# MYC_Klimasensor.net
KiCad netlist of a schematic drawn in EAGLE
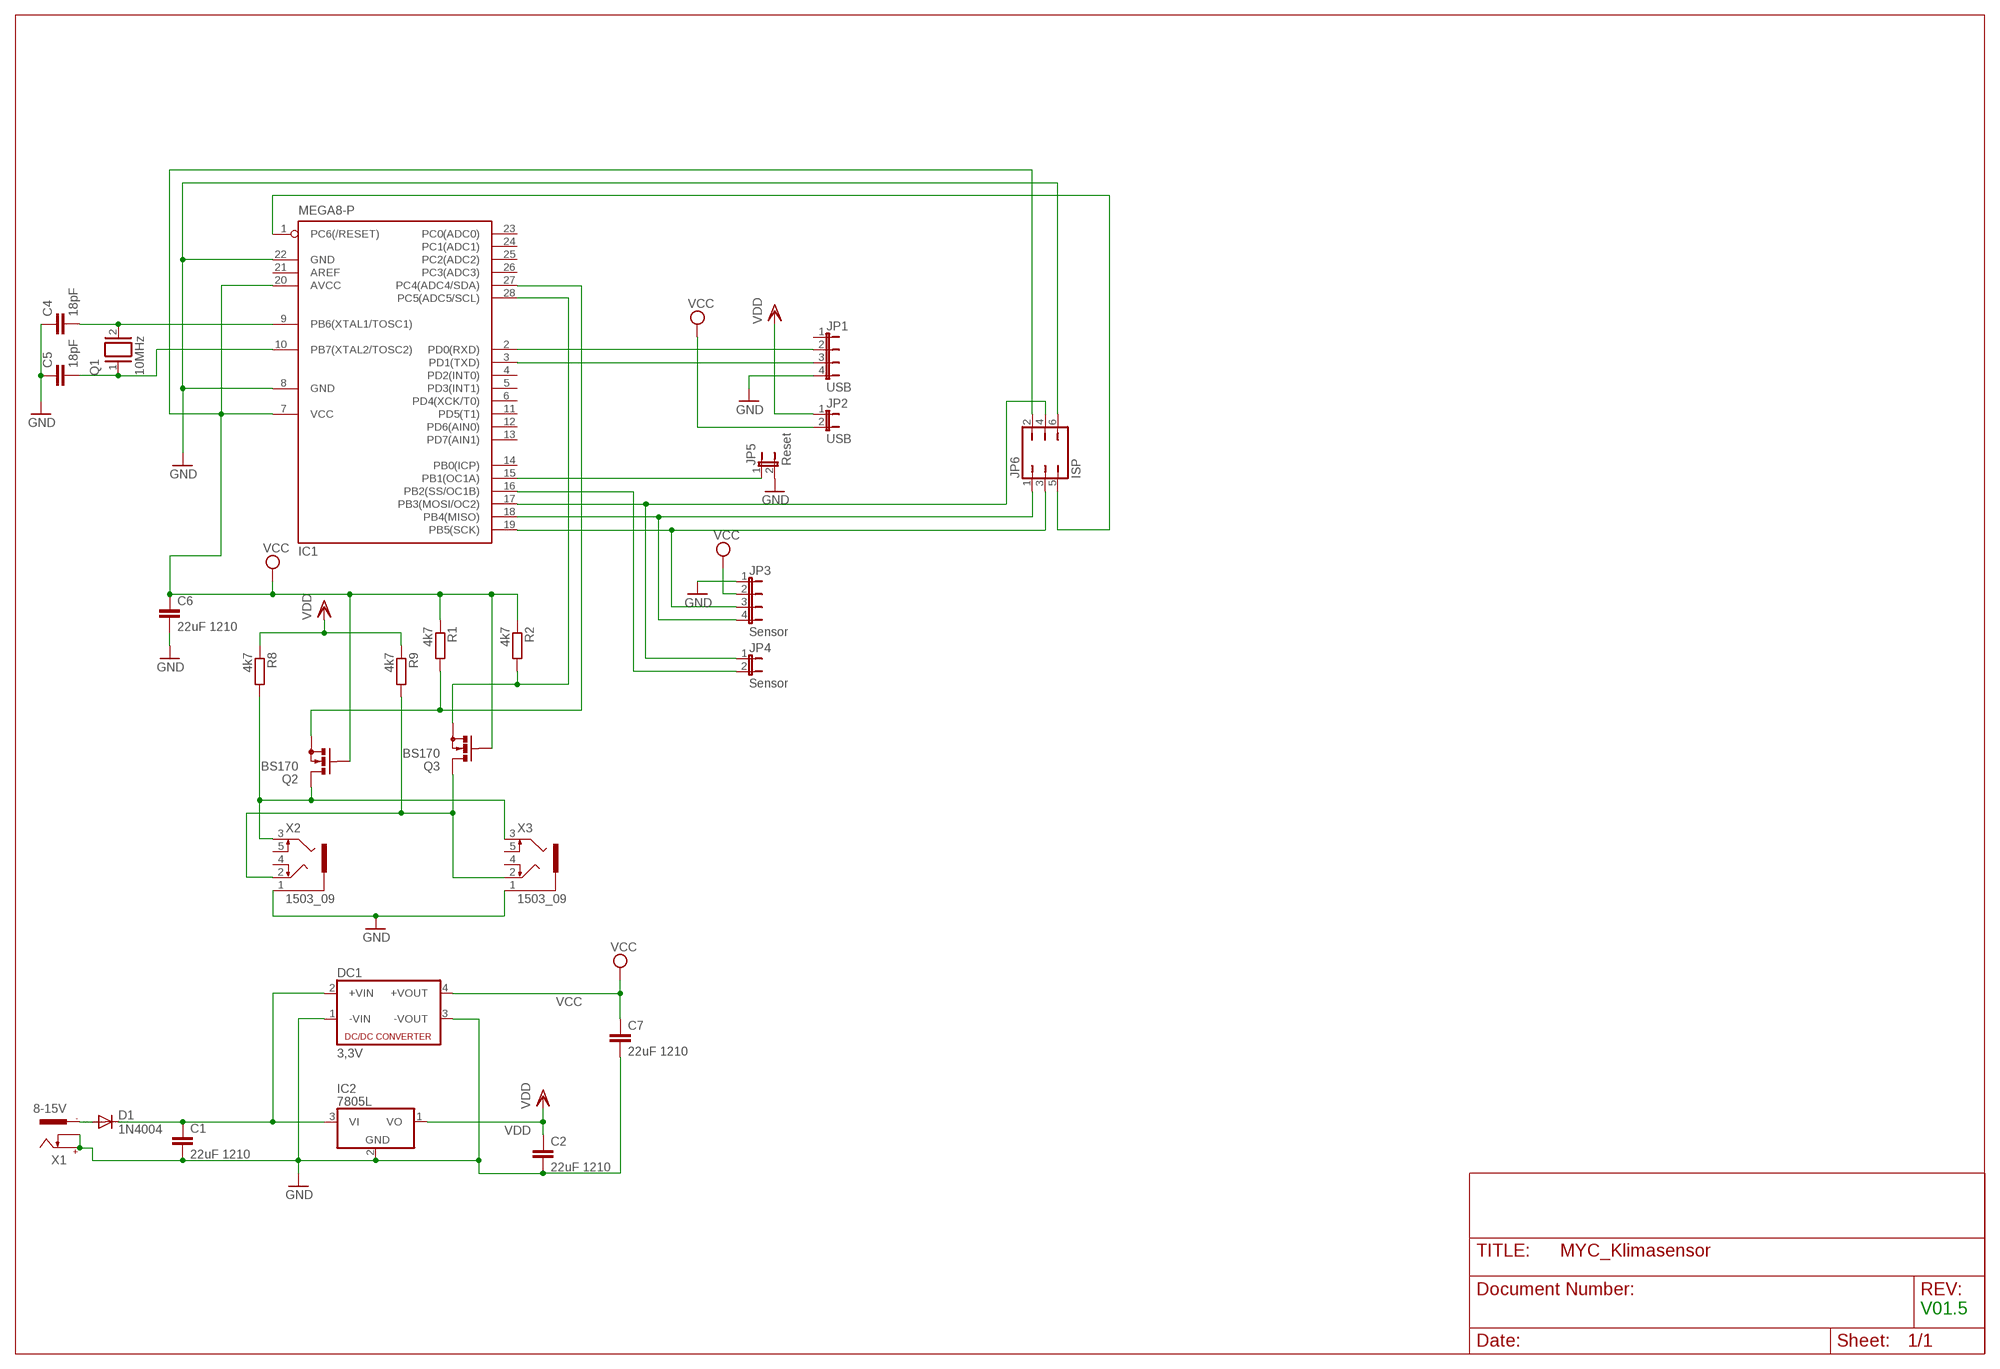
[diagram p0: schematic, sheet 1]

(export (version "E")
  (design (tool "Eeschema 10.0.6"))
  (components
    (comp (ref "C1")
      (value "22uF 1210")
      (footprint "eagle-import:C1206")
      (libsource (lib "eagle-import") (part "C-EUC1206"))
    )
    (comp (ref "C2")
      (value "22uF 1210")
      (footprint "eagle-import:C1206")
      (libsource (lib "eagle-import") (part "C-EUC1206"))
    )
    (comp (ref "C4")
      (value "18pF")
      (footprint "eagle-import:C025-025X050")
      (libsource (lib "eagle-import") (part "resistor_C-EU025-025X050"))
    )
    (comp (ref "C5")
      (value "18pF")
      (footprint "eagle-import:C025-025X050")
      (libsource (lib "eagle-import") (part "resistor_C-EU025-025X050"))
    )
    (comp (ref "C6")
      (value "22uF 1210")
      (footprint "eagle-import:C1206")
      (libsource (lib "eagle-import") (part "C-EUC1206"))
    )
    (comp (ref "C7")
      (value "22uF 1210")
      (footprint "eagle-import:C1206")
      (libsource (lib "eagle-import") (part "C-EUC1206"))
    )
    (comp (ref "D1")
      (value "1N4004")
      (footprint "eagle-import:DO41-10")
      (libsource (lib "eagle-import") (part "1N4004"))
    )
    (comp (ref "DC1")
      (value "3,3V")
      (footprint "eagle-import:NME")
      (fields (field (name "MF") "C & D TECHNOLOGIES, INC") (field (name "MPN") "NME1205D"))
      (libsource (lib "eagle-import") (part "NME"))
    )
    (comp (ref "IC1")
      (value "MEGA8-P")
      (footprint "eagle-import:DIL28-3")
      (libsource (lib "eagle-import") (part "MEGA8-P"))
    )
    (comp (ref "IC2")
      (value "7805L")
      (footprint "eagle-import:TO92")
      (libsource (lib "eagle-import") (part "78L05"))
    )
    (comp (ref "JP1")
      (value "USB")
      (footprint "eagle-import:JP4")
      (libsource (lib "eagle-import") (part "JP4E"))
    )
    (comp (ref "JP2")
      (value "USB")
      (footprint "eagle-import:JP1")
      (libsource (lib "eagle-import") (part "JP1E"))
    )
    (comp (ref "JP3")
      (value "Sensor")
      (footprint "eagle-import:JP4")
      (libsource (lib "eagle-import") (part "JP4E"))
    )
    (comp (ref "JP4")
      (value "Sensor")
      (footprint "eagle-import:JP1")
      (libsource (lib "eagle-import") (part "JP1E"))
    )
    (comp (ref "JP5")
      (value "Reset")
      (footprint "eagle-import:JP1")
      (libsource (lib "eagle-import") (part "JP1E"))
    )
    (comp (ref "JP6")
      (value "ISP")
      (footprint "eagle-import:JP3Q")
      (libsource (lib "eagle-import") (part "JP3Q"))
    )
    (comp (ref "Q1")
      (value "10MHz")
      (footprint "eagle-import:QS")
      (libsource (lib "eagle-import") (part "XTAL/S"))
    )
    (comp (ref "Q2")
      (value "BS170")
      (footprint "eagle-import:SOT54E")
      (libsource (lib "eagle-import") (part "BS170"))
    )
    (comp (ref "Q3")
      (value "BS170")
      (footprint "eagle-import:SOT54E")
      (libsource (lib "eagle-import") (part "BS170"))
    )
    (comp (ref "R1")
      (value "4k7")
      (footprint "eagle-import:R1206")
      (libsource (lib "eagle-import") (part "R-EU_R1206"))
    )
    (comp (ref "R2")
      (value "4k7")
      (footprint "eagle-import:R1206")
      (libsource (lib "eagle-import") (part "R-EU_R1206"))
    )
    (comp (ref "R8")
      (value "4k7")
      (footprint "eagle-import:R1206")
      (libsource (lib "eagle-import") (part "R-EU_R1206"))
    )
    (comp (ref "R9")
      (value "4k7")
      (footprint "eagle-import:R1206")
      (libsource (lib "eagle-import") (part "R-EU_R1206"))
    )
    (comp (ref "X1")
      (value "8-15V")
      (footprint "eagle-import:737992-5")
      (libsource (lib "eagle-import") (part "737992-55"))
    )
    (comp (ref "X2")
      (value "1503_09")
      (footprint "eagle-import:1503_09")
      (libsource (lib "eagle-import") (part "1503_09"))
    )
    (comp (ref "X3")
      (value "1503_09")
      (footprint "eagle-import:1503_09")
      (libsource (lib "eagle-import") (part "1503_09"))
    )
  )
  (nets
    (net (code "1") (name "GND") (class "Default")
      (node (ref "C1") (pin "2") (pinfunction "2_2") (pintype "passive"))
      (node (ref "C2") (pin "2") (pinfunction "2_2") (pintype "passive"))
      (node (ref "C4") (pin "1") (pinfunction "1_1") (pintype "passive"))
      (node (ref "C5") (pin "1") (pinfunction "1_1") (pintype "passive"))
      (node (ref "C6") (pin "2") (pinfunction "2_2") (pintype "passive"))
      (node (ref "C7") (pin "2") (pinfunction "2_2") (pintype "passive"))
      (node (ref "DC1") (pin "1") (pinfunction "-VIN_1") (pintype "passive"))
      (node (ref "DC1") (pin "3") (pinfunction "-VOUT_3") (pintype "passive"))
      (node (ref "IC1") (pin "22") (pinfunction "GND_22") (pintype "power_in"))
      (node (ref "IC1") (pin "8") (pinfunction "GND_8") (pintype "power_in"))
      (node (ref "IC2") (pin "2") (pinfunction "GND_2") (pintype "passive"))
      (node (ref "JP1") (pin "4") (pinfunction "4_4") (pintype "passive"))
      (node (ref "JP3") (pin "1") (pinfunction "1_1") (pintype "passive"))
      (node (ref "JP5") (pin "2") (pinfunction "2_2") (pintype "passive"))
      (node (ref "JP6") (pin "6") (pinfunction "6_6") (pintype "passive"))
      (node (ref "X1") (pin "+") (pinfunction "+_+") (pintype "passive"))
      (node (ref "X1") (pin "K") (pinfunction "K_K") (pintype "passive"))
      (node (ref "X2") (pin "1") (pinfunction "1_1") (pintype "passive"))
      (node (ref "X3") (pin "1") (pinfunction "1_1") (pintype "passive"))
    )
    (net (code "2") (name "Net-(D1-PadA)") (class "Default")
      (node (ref "D1") (pin "A") (pinfunction "A_A") (pintype "passive"))
      (node (ref "X1") (pin "-1") (pinfunction "-1_-1") (pintype "passive"))
    )
    (net (code "3") (name "Net-(DC1-+VIN)") (class "Default")
      (node (ref "C1") (pin "1") (pinfunction "1_1") (pintype "passive"))
      (node (ref "D1") (pin "C") (pinfunction "C_C") (pintype "passive"))
      (node (ref "DC1") (pin "2") (pinfunction "+VIN_2") (pintype "passive"))
      (node (ref "IC2") (pin "3") (pinfunction "VI_3") (pintype "input"))
    )
    (net (code "4") (name "Net-(IC1-PB1(OC1A))") (class "Default")
      (node (ref "IC1") (pin "15") (pinfunction "PB1(OC1A)_15") (pintype "bidirectional"))
      (node (ref "JP5") (pin "1") (pinfunction "1_1") (pintype "passive"))
    )
    (net (code "5") (name "Net-(IC1-PB2(SS{slash}OC1B))") (class "Default")
      (node (ref "IC1") (pin "16") (pinfunction "PB2(SS/OC1B)_16") (pintype "bidirectional"))
      (node (ref "JP4") (pin "2") (pinfunction "2_2") (pintype "passive"))
    )
    (net (code "6") (name "Net-(IC1-PB3(MOSI{slash}OC2))") (class "Default")
      (node (ref "IC1") (pin "17") (pinfunction "PB3(MOSI/OC2)_17") (pintype "bidirectional"))
      (node (ref "JP4") (pin "1") (pinfunction "1_1") (pintype "passive"))
      (node (ref "JP6") (pin "4") (pinfunction "4_4") (pintype "passive"))
    )
    (net (code "7") (name "Net-(IC1-PB4(MISO))") (class "Default")
      (node (ref "IC1") (pin "18") (pinfunction "PB4(MISO)_18") (pintype "bidirectional"))
      (node (ref "JP3") (pin "4") (pinfunction "4_4") (pintype "passive"))
      (node (ref "JP6") (pin "1") (pinfunction "1_1") (pintype "passive"))
    )
    (net (code "8") (name "Net-(IC1-PB5(SCK))") (class "Default")
      (node (ref "IC1") (pin "19") (pinfunction "PB5(SCK)_19") (pintype "bidirectional"))
      (node (ref "JP3") (pin "3") (pinfunction "3_3") (pintype "passive"))
      (node (ref "JP6") (pin "3") (pinfunction "3_3") (pintype "passive"))
    )
    (net (code "9") (name "Net-(IC1-PB6(XTAL1{slash}TOSC1))") (class "Default")
      (node (ref "C4") (pin "2") (pinfunction "2_2") (pintype "passive"))
      (node (ref "IC1") (pin "9") (pinfunction "PB6(XTAL1/TOSC1)_9") (pintype "bidirectional"))
      (node (ref "Q1") (pin "2") (pinfunction "2_2") (pintype "passive"))
    )
    (net (code "10") (name "Net-(IC1-PB7(XTAL2{slash}TOSC2))") (class "Default")
      (node (ref "C5") (pin "2") (pinfunction "2_2") (pintype "passive"))
      (node (ref "IC1") (pin "10") (pinfunction "PB7(XTAL2/TOSC2)_10") (pintype "bidirectional"))
      (node (ref "Q1") (pin "1") (pinfunction "1_1") (pintype "passive"))
    )
    (net (code "11") (name "Net-(IC1-PC4(ADC4{slash}SDA))") (class "Default")
      (node (ref "IC1") (pin "27") (pinfunction "PC4(ADC4/SDA)_27") (pintype "bidirectional"))
      (node (ref "Q2") (pin "S") (pinfunction "S_S") (pintype "passive"))
      (node (ref "R1") (pin "2") (pinfunction "2_2") (pintype "passive"))
    )
    (net (code "12") (name "Net-(IC1-PC5(ADC5{slash}SCL))") (class "Default")
      (node (ref "IC1") (pin "28") (pinfunction "PC5(ADC5/SCL)_28") (pintype "bidirectional"))
      (node (ref "Q3") (pin "S") (pinfunction "S_S") (pintype "passive"))
      (node (ref "R2") (pin "2") (pinfunction "2_2") (pintype "passive"))
    )
    (net (code "13") (name "Net-(IC1-PC6({slash}RESET))") (class "Default")
      (node (ref "IC1") (pin "1") (pinfunction "PC6(/RESET)_1") (pintype "bidirectional"))
      (node (ref "JP6") (pin "5") (pinfunction "5_5") (pintype "passive"))
    )
    (net (code "14") (name "Net-(IC1-PD0(RXD))") (class "Default")
      (node (ref "IC1") (pin "2") (pinfunction "PD0(RXD)_2") (pintype "bidirectional"))
      (node (ref "JP1") (pin "2") (pinfunction "2_2") (pintype "passive"))
    )
    (net (code "15") (name "Net-(IC1-PD1(TXD))") (class "Default")
      (node (ref "IC1") (pin "3") (pinfunction "PD1(TXD)_3") (pintype "bidirectional"))
      (node (ref "JP1") (pin "3") (pinfunction "3_3") (pintype "passive"))
    )
    (net (code "16") (name "Net-(Q2-PadD)") (class "Default")
      (node (ref "Q2") (pin "D") (pinfunction "D_D") (pintype "passive"))
      (node (ref "R8") (pin "2") (pinfunction "2_2") (pintype "passive"))
      (node (ref "X2") (pin "3") (pinfunction "3_3") (pintype "passive"))
      (node (ref "X3") (pin "3") (pinfunction "3_3") (pintype "passive"))
    )
    (net (code "17") (name "Net-(Q3-PadD)") (class "Default")
      (node (ref "Q3") (pin "D") (pinfunction "D_D") (pintype "passive"))
      (node (ref "R9") (pin "2") (pinfunction "2_2") (pintype "passive"))
      (node (ref "X2") (pin "2") (pinfunction "2_2") (pintype "passive"))
      (node (ref "X3") (pin "2") (pinfunction "2_2") (pintype "passive"))
    )
    (net (code "18") (name "VCC") (class "Default")
      (node (ref "C6") (pin "1") (pinfunction "1_1") (pintype "passive"))
      (node (ref "C7") (pin "1") (pinfunction "1_1") (pintype "passive"))
      (node (ref "DC1") (pin "4") (pinfunction "+VOUT_4") (pintype "passive"))
      (node (ref "IC1") (pin "20") (pinfunction "AVCC_20") (pintype "power_in"))
      (node (ref "IC1") (pin "7") (pinfunction "VCC_7") (pintype "power_in"))
      (node (ref "JP2") (pin "2") (pinfunction "2_2") (pintype "passive"))
      (node (ref "JP3") (pin "2") (pinfunction "2_2") (pintype "passive"))
      (node (ref "JP6") (pin "2") (pinfunction "2_2") (pintype "passive"))
      (node (ref "Q2") (pin "G") (pinfunction "G_G") (pintype "passive"))
      (node (ref "Q3") (pin "G") (pinfunction "G_G") (pintype "passive"))
      (node (ref "R1") (pin "1") (pinfunction "1_1") (pintype "passive"))
      (node (ref "R2") (pin "1") (pinfunction "1_1") (pintype "passive"))
    )
    (net (code "19") (name "VDD") (class "Default")
      (node (ref "C2") (pin "1") (pinfunction "1_1") (pintype "passive"))
      (node (ref "IC2") (pin "1") (pinfunction "VO_1") (pintype "passive"))
      (node (ref "JP2") (pin "1") (pinfunction "1_1") (pintype "passive"))
      (node (ref "R8") (pin "1") (pinfunction "1_1") (pintype "passive"))
      (node (ref "R9") (pin "1") (pinfunction "1_1") (pintype "passive"))
    )
    (net (code "20") (name "unconnected-(IC1-AREF-Pad21)") (class "Default")
      (node (ref "IC1") (pin "21") (pinfunction "AREF_21") (pintype "passive"))
    )
    (net (code "21") (name "unconnected-(IC1-PB0(ICP)-Pad14)") (class "Default")
      (node (ref "IC1") (pin "14") (pinfunction "PB0(ICP)_14") (pintype "bidirectional"))
    )
    (net (code "22") (name "unconnected-(IC1-PC0(ADC0)-Pad23)") (class "Default")
      (node (ref "IC1") (pin "23") (pinfunction "PC0(ADC0)_23") (pintype "bidirectional"))
    )
    (net (code "23") (name "unconnected-(IC1-PC1(ADC1)-Pad24)") (class "Default")
      (node (ref "IC1") (pin "24") (pinfunction "PC1(ADC1)_24") (pintype "bidirectional"))
    )
    (net (code "24") (name "unconnected-(IC1-PC2(ADC2)-Pad25)") (class "Default")
      (node (ref "IC1") (pin "25") (pinfunction "PC2(ADC2)_25") (pintype "bidirectional"))
    )
    (net (code "25") (name "unconnected-(IC1-PC3(ADC3)-Pad26)") (class "Default")
      (node (ref "IC1") (pin "26") (pinfunction "PC3(ADC3)_26") (pintype "bidirectional"))
    )
    (net (code "26") (name "unconnected-(IC1-PD2(INT0)-Pad4)") (class "Default")
      (node (ref "IC1") (pin "4") (pinfunction "PD2(INT0)_4") (pintype "bidirectional"))
    )
    (net (code "27") (name "unconnected-(IC1-PD3(INT1)-Pad5)") (class "Default")
      (node (ref "IC1") (pin "5") (pinfunction "PD3(INT1)_5") (pintype "bidirectional"))
    )
    (net (code "28") (name "unconnected-(IC1-PD4(XCK{slash}T0)-Pad6)") (class "Default")
      (node (ref "IC1") (pin "6") (pinfunction "PD4(XCK/T0)_6") (pintype "bidirectional"))
    )
    (net (code "29") (name "unconnected-(IC1-PD5(T1)-Pad11)") (class "Default")
      (node (ref "IC1") (pin "11") (pinfunction "PD5(T1)_11") (pintype "bidirectional"))
    )
    (net (code "30") (name "unconnected-(IC1-PD6(AIN0)-Pad12)") (class "Default")
      (node (ref "IC1") (pin "12") (pinfunction "PD6(AIN0)_12") (pintype "bidirectional"))
    )
    (net (code "31") (name "unconnected-(IC1-PD7(AIN1)-Pad13)") (class "Default")
      (node (ref "IC1") (pin "13") (pinfunction "PD7(AIN1)_13") (pintype "bidirectional"))
    )
    (net (code "32") (name "unconnected-(JP1-Pad1)") (class "Default")
      (node (ref "JP1") (pin "1") (pinfunction "1_1") (pintype "passive"))
    )
    (net (code "33") (name "unconnected-(X1-Pad-2)") (class "Default")
      (node (ref "X1") (pin "-2") (pinfunction "-2_-2") (pintype "passive"))
    )
    (net (code "34") (name "unconnected-(X2-Pad4)") (class "Default")
      (node (ref "X2") (pin "4") (pinfunction "4_4") (pintype "passive"))
    )
    (net (code "35") (name "unconnected-(X2-Pad5)") (class "Default")
      (node (ref "X2") (pin "5") (pinfunction "5_5") (pintype "passive"))
    )
    (net (code "36") (name "unconnected-(X3-Pad4)") (class "Default")
      (node (ref "X3") (pin "4") (pinfunction "4_4") (pintype "passive"))
    )
    (net (code "37") (name "unconnected-(X3-Pad5)") (class "Default")
      (node (ref "X3") (pin "5") (pinfunction "5_5") (pintype "passive"))
    )
  )
)
